# CW313_20_Pin_Connector.net
KiCad netlist of a schematic drawn in Altium Designer
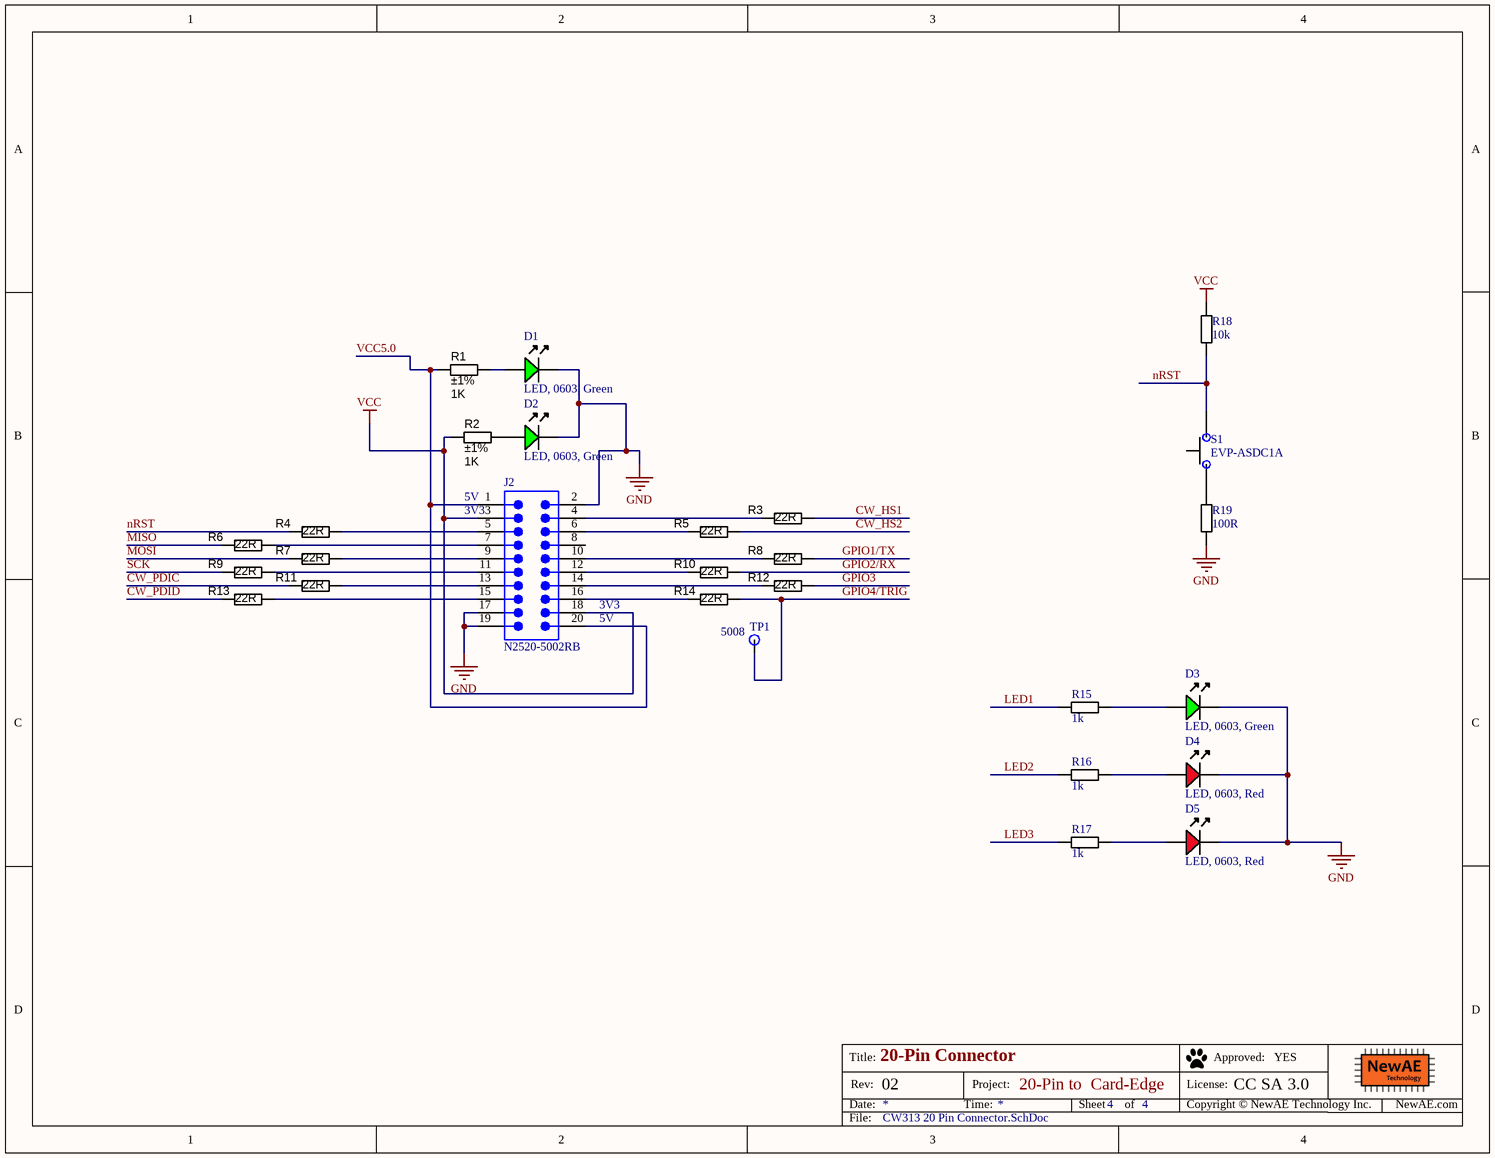
[diagram p0: CW313 20 Pin Connector.SchDoc]

(export (version "E")
  (design (tool "Eeschema 10.0.6"))
  (components
    (comp (ref "D1")
      (value "LED, 0603, Green")
      (footprint "LED-0603-GREEN")
      (description "Chip LED, Green")
      (fields (field (name "PART NUMBER") "LEDCHIP_0603_GREEN"))
      (libsource (lib "NewAE_AltiumLib") (part "LED_GREEN"))
    )
    (comp (ref "D2")
      (value "LED, 0603, Green")
      (footprint "LED-0603-GREEN")
      (description "Chip LED, Green")
      (fields (field (name "PART NUMBER") "LEDCHIP_0603_GREEN"))
      (libsource (lib "NewAE_AltiumLib") (part "LED_GREEN"))
    )
    (comp (ref "D3")
      (value "LED, 0603, Green")
      (footprint "LED-0603-GREEN")
      (description "Chip LED, Green")
      (fields (field (name "PART NUMBER") "LEDCHIP_0603_GREEN"))
      (libsource (lib "NewAE_AltiumLib") (part "LED_GREEN"))
    )
    (comp (ref "D4")
      (value "LED, 0603, Red")
      (footprint "LED-0603-RED")
      (description "Chip LED, Red")
      (fields (field (name "PART NUMBER") "LEDCHIP_0603_RED"))
      (libsource (lib "NewAE_AltiumLib") (part "LED_RED"))
    )
    (comp (ref "D5")
      (value "LED, 0603, Red")
      (footprint "LED-0603-RED")
      (description "Chip LED, Red")
      (fields (field (name "PART NUMBER") "LEDCHIP_0603_RED"))
      (libsource (lib "NewAE_AltiumLib") (part "LED_RED"))
    )
    (comp (ref "J2")
      (value "N2520-5002RB")
      (footprint "NAE-PCB-CW-1000-0001-01")
      (description "20 Pin R/A Shrouded Header")
      (fields (field (name "MANUFACTURER") "3M"))
      (libsource (lib "NewAE_AltiumLib") (part "NAE-CW-1000-0001-01"))
    )
    (comp (ref "R1")
      (value "1K")
      (footprint "RESC1608X55N")
      (description "Resistor SMD chip 1k Ohm 0.1W 1% 0603")
      (fields (field (name "TOLERANCE") "±1%") (field (name "Comment") "Thick Film"))
      (libsource (lib "PBL - Resistors") (part "RES_1K_0603_1%"))
    )
    (comp (ref "R2")
      (value "1K")
      (footprint "RESC1608X55N")
      (description "Resistor SMD chip 1k Ohm 0.1W 1% 0603")
      (fields (field (name "TOLERANCE") "±1%") (field (name "Comment") "Thick Film"))
      (libsource (lib "PBL - Resistors") (part "RES_1K_0603_1%"))
    )
    (comp (ref "R3")
      (value "22R")
      (footprint "RESC1608X55N")
      (description "Resistor SMD chip 22 Ohm 0.1W 5% 0603")
      (fields (field (name "TOLERANCE") "±5%") (field (name "Comment") "Thick Film"))
      (libsource (lib "PBL - Resistors") (part "RES_22R_0603_5%"))
    )
    (comp (ref "R4")
      (value "22R")
      (footprint "RESC1608X55N")
      (description "Resistor SMD chip 22 Ohm 0.1W 5% 0603")
      (fields (field (name "TOLERANCE") "±5%") (field (name "Comment") "Thick Film"))
      (libsource (lib "PBL - Resistors") (part "RES_22R_0603_5%"))
    )
    (comp (ref "R5")
      (value "22R")
      (footprint "RESC1608X55N")
      (description "Resistor SMD chip 22 Ohm 0.1W 5% 0603")
      (fields (field (name "TOLERANCE") "±5%") (field (name "Comment") "Thick Film"))
      (libsource (lib "PBL - Resistors") (part "RES_22R_0603_5%"))
    )
    (comp (ref "R6")
      (value "22R")
      (footprint "RESC1608X55N")
      (description "Resistor SMD chip 22 Ohm 0.1W 5% 0603")
      (fields (field (name "TOLERANCE") "±5%") (field (name "Comment") "Thick Film"))
      (libsource (lib "PBL - Resistors") (part "RES_22R_0603_5%"))
    )
    (comp (ref "R7")
      (value "22R")
      (footprint "RESC1608X55N")
      (description "Resistor SMD chip 22 Ohm 0.1W 5% 0603")
      (fields (field (name "TOLERANCE") "±5%") (field (name "Comment") "Thick Film"))
      (libsource (lib "PBL - Resistors") (part "RES_22R_0603_5%"))
    )
    (comp (ref "R8")
      (value "22R")
      (footprint "RESC1608X55N")
      (description "Resistor SMD chip 22 Ohm 0.1W 5% 0603")
      (fields (field (name "TOLERANCE") "±5%") (field (name "Comment") "Thick Film"))
      (libsource (lib "PBL - Resistors") (part "RES_22R_0603_5%"))
    )
    (comp (ref "R9")
      (value "22R")
      (footprint "RESC1608X55N")
      (description "Resistor SMD chip 22 Ohm 0.1W 5% 0603")
      (fields (field (name "TOLERANCE") "±5%") (field (name "Comment") "Thick Film"))
      (libsource (lib "PBL - Resistors") (part "RES_22R_0603_5%"))
    )
    (comp (ref "R10")
      (value "22R")
      (footprint "RESC1608X55N")
      (description "Resistor SMD chip 22 Ohm 0.1W 5% 0603")
      (fields (field (name "TOLERANCE") "±5%") (field (name "Comment") "Thick Film"))
      (libsource (lib "PBL - Resistors") (part "RES_22R_0603_5%"))
    )
    (comp (ref "R11")
      (value "22R")
      (footprint "RESC1608X55N")
      (description "Resistor SMD chip 22 Ohm 0.1W 5% 0603")
      (fields (field (name "TOLERANCE") "±5%") (field (name "Comment") "Thick Film"))
      (libsource (lib "PBL - Resistors") (part "RES_22R_0603_5%"))
    )
    (comp (ref "R12")
      (value "22R")
      (footprint "RESC1608X55N")
      (description "Resistor SMD chip 22 Ohm 0.1W 5% 0603")
      (fields (field (name "TOLERANCE") "±5%") (field (name "Comment") "Thick Film"))
      (libsource (lib "PBL - Resistors") (part "RES_22R_0603_5%"))
    )
    (comp (ref "R13")
      (value "22R")
      (footprint "RESC1608X55N")
      (description "Resistor SMD chip 22 Ohm 0.1W 5% 0603")
      (fields (field (name "TOLERANCE") "±5%") (field (name "Comment") "Thick Film"))
      (libsource (lib "PBL - Resistors") (part "RES_22R_0603_5%"))
    )
    (comp (ref "R14")
      (value "22R")
      (footprint "RESC1608X55N")
      (description "Resistor SMD chip 22 Ohm 0.1W 5% 0603")
      (fields (field (name "TOLERANCE") "±5%") (field (name "Comment") "Thick Film"))
      (libsource (lib "PBL - Resistors") (part "RES_22R_0603_5%"))
    )
    (comp (ref "R15")
      (value "1k")
      (footprint "RESC1608X55N")
      (description "1k res, 0603, 1%, 1/10W")
      (fields (field (name "PART NUMBER") "RCHIP-1K-0603") (field (name "TOLERANCE") "1%"))
      (libsource (lib "NewAE_AltiumLib") (part "RES-EU"))
    )
    (comp (ref "R16")
      (value "1k")
      (footprint "RESC1608X55N")
      (description "1k res, 0603, 1%, 1/10W")
      (fields (field (name "PART NUMBER") "RCHIP-1K-0603") (field (name "TOLERANCE") "1%"))
      (libsource (lib "NewAE_AltiumLib") (part "RES-EU"))
    )
    (comp (ref "R17")
      (value "1k")
      (footprint "RESC1608X55N")
      (description "1k res, 0603, 1%, 1/10W")
      (fields (field (name "PART NUMBER") "RCHIP-1K-0603") (field (name "TOLERANCE") "1%"))
      (libsource (lib "NewAE_AltiumLib") (part "RES-EU"))
    )
    (comp (ref "R18")
      (value "10k")
      (footprint "RESC1608X55N")
      (description "10k res, 0603, 1%, 1/10W")
      (fields (field (name "PART NUMBER") "RCHIP-10K-0603") (field (name "TOLERANCE") "1%"))
      (libsource (lib "") (part "RES-EU_1"))
    )
    (comp (ref "R19")
      (value "100R")
      (footprint "RESC1608X55N")
      (description "100R res, 0603, 1%, 1/10W")
      (fields (field (name "PART NUMBER") "RCHIP-100R-0603") (field (name "TOLERANCE") "1%"))
      (libsource (lib "") (part "RES-EU_1"))
    )
    (comp (ref "S1")
      (value "EVP-ASDC1A")
      (footprint "EVPAS")
      (description "Pushbutton, SMD, 2.5NM force, NO")
      (libsource (lib "NewAE_AltiumLib") (part "SW_PB_NO_2PIN"))
    )
    (comp (ref "TP1")
      (value "5008")
      (footprint "KEYSTONE5008")
      (description "TEST POINT PC COMPACT .063\"D ORG")
      (fields (field (name "PART NUMBER") "KEYSTONE_5008"))
      (libsource (lib "NewAE_AltiumLib") (part "KEYSTONE_5008"))
    )
  )
  (nets
    (net (code "1") (name "/CW_HS1") (class "Default")
      (node (ref "R3") (pin "2") (pinfunction "2_2") (pintype "passive"))
    )
    (net (code "2") (name "/CW_HS2") (class "Default")
      (node (ref "R5") (pin "2") (pinfunction "2_2") (pintype "passive"))
    )
    (net (code "3") (name "/CW_PDIC") (class "Default")
      (node (ref "R11") (pin "1") (pinfunction "1_1") (pintype "passive"))
    )
    (net (code "4") (name "/CW_PDID") (class "Default")
      (node (ref "R13") (pin "1") (pinfunction "1_1") (pintype "passive"))
    )
    (net (code "5") (name "/GPIO1{slash}TX") (class "Default")
      (node (ref "R8") (pin "2") (pinfunction "2_2") (pintype "passive"))
    )
    (net (code "6") (name "/GPIO2{slash}RX") (class "Default")
      (node (ref "R10") (pin "2") (pinfunction "2_2") (pintype "passive"))
    )
    (net (code "7") (name "/GPIO3") (class "Default")
      (node (ref "R12") (pin "2") (pinfunction "2_2") (pintype "passive"))
    )
    (net (code "8") (name "/GPIO4{slash}TRIG") (class "Default")
      (node (ref "R14") (pin "2") (pinfunction "2_2") (pintype "passive"))
      (node (ref "TP1") (pin "1") (pinfunction "1_1") (pintype "passive"))
    )
    (net (code "9") (name "/LED1") (class "Default")
      (node (ref "R15") (pin "1") (pinfunction "1_1") (pintype "passive"))
    )
    (net (code "10") (name "/LED2") (class "Default")
      (node (ref "R16") (pin "1") (pinfunction "1_1") (pintype "passive"))
    )
    (net (code "11") (name "/LED3") (class "Default")
      (node (ref "R17") (pin "1") (pinfunction "1_1") (pintype "passive"))
    )
    (net (code "12") (name "/MISO") (class "Default")
      (node (ref "R6") (pin "1") (pinfunction "1_1") (pintype "passive"))
    )
    (net (code "13") (name "/MOSI") (class "Default")
      (node (ref "R7") (pin "1") (pinfunction "1_1") (pintype "passive"))
    )
    (net (code "14") (name "/SCK") (class "Default")
      (node (ref "R9") (pin "1") (pinfunction "1_1") (pintype "passive"))
    )
    (net (code "15") (name "/VCC5.0") (class "Default")
      (node (ref "J2") (pin "1") (pinfunction "1_1") (pintype "passive"))
      (node (ref "J2") (pin "20") (pinfunction "20_20") (pintype "passive"))
      (node (ref "R1") (pin "2") (pinfunction "2_2") (pintype "passive"))
    )
    (net (code "16") (name "/nRST") (class "Default")
      (node (ref "R18") (pin "2") (pinfunction "2_2") (pintype "passive"))
      (node (ref "R4") (pin "1") (pinfunction "1_1") (pintype "passive"))
      (node (ref "S1") (pin "2") (pinfunction "IN_2") (pintype "passive"))
    )
    (net (code "17") (name "GND") (class "Default")
      (node (ref "D1") (pin "K") (pinfunction "K_K") (pintype "passive"))
      (node (ref "D2") (pin "K") (pinfunction "K_K") (pintype "passive"))
      (node (ref "D3") (pin "K") (pinfunction "K_K") (pintype "passive"))
      (node (ref "D4") (pin "K") (pinfunction "K_K") (pintype "passive"))
      (node (ref "D5") (pin "K") (pinfunction "K_K") (pintype "passive"))
      (node (ref "J2") (pin "17") (pinfunction "17_17") (pintype "passive"))
      (node (ref "J2") (pin "19") (pinfunction "19_19") (pintype "passive"))
      (node (ref "J2") (pin "2") (pinfunction "2_2") (pintype "passive"))
      (node (ref "R19") (pin "2") (pinfunction "2_2") (pintype "passive"))
    )
    (net (code "18") (name "Net-(D1-PadA)") (class "Default")
      (node (ref "D1") (pin "A") (pinfunction "A_A") (pintype "passive"))
      (node (ref "R1") (pin "1") (pinfunction "1_1") (pintype "passive"))
    )
    (net (code "19") (name "Net-(D2-PadA)") (class "Default")
      (node (ref "D2") (pin "A") (pinfunction "A_A") (pintype "passive"))
      (node (ref "R2") (pin "1") (pinfunction "1_1") (pintype "passive"))
    )
    (net (code "20") (name "Net-(D3-PadA)") (class "Default")
      (node (ref "D3") (pin "A") (pinfunction "A_A") (pintype "passive"))
      (node (ref "R15") (pin "2") (pinfunction "2_2") (pintype "passive"))
    )
    (net (code "21") (name "Net-(D4-PadA)") (class "Default")
      (node (ref "D4") (pin "A") (pinfunction "A_A") (pintype "passive"))
      (node (ref "R16") (pin "2") (pinfunction "2_2") (pintype "passive"))
    )
    (net (code "22") (name "Net-(D5-PadA)") (class "Default")
      (node (ref "D5") (pin "A") (pinfunction "A_A") (pintype "passive"))
      (node (ref "R17") (pin "2") (pinfunction "2_2") (pintype "passive"))
    )
    (net (code "23") (name "Net-(J2-Pad4)") (class "Default")
      (node (ref "J2") (pin "4") (pinfunction "4_4") (pintype "passive"))
      (node (ref "R3") (pin "1") (pinfunction "1_1") (pintype "passive"))
    )
    (net (code "24") (name "Net-(J2-Pad5)") (class "Default")
      (node (ref "J2") (pin "5") (pinfunction "5_5") (pintype "passive"))
      (node (ref "R4") (pin "2") (pinfunction "2_2") (pintype "passive"))
    )
    (net (code "25") (name "Net-(J2-Pad6)") (class "Default")
      (node (ref "J2") (pin "6") (pinfunction "6_6") (pintype "passive"))
      (node (ref "R5") (pin "1") (pinfunction "1_1") (pintype "passive"))
    )
    (net (code "26") (name "Net-(J2-Pad7)") (class "Default")
      (node (ref "J2") (pin "7") (pinfunction "7_7") (pintype "passive"))
      (node (ref "R6") (pin "2") (pinfunction "2_2") (pintype "passive"))
    )
    (net (code "27") (name "Net-(J2-Pad9)") (class "Default")
      (node (ref "J2") (pin "9") (pinfunction "9_9") (pintype "passive"))
      (node (ref "R7") (pin "2") (pinfunction "2_2") (pintype "passive"))
    )
    (net (code "28") (name "Net-(J2-Pad10)") (class "Default")
      (node (ref "J2") (pin "10") (pinfunction "10_10") (pintype "passive"))
      (node (ref "R8") (pin "1") (pinfunction "1_1") (pintype "passive"))
    )
    (net (code "29") (name "Net-(J2-Pad11)") (class "Default")
      (node (ref "J2") (pin "11") (pinfunction "11_11") (pintype "passive"))
      (node (ref "R9") (pin "2") (pinfunction "2_2") (pintype "passive"))
    )
    (net (code "30") (name "Net-(J2-Pad12)") (class "Default")
      (node (ref "J2") (pin "12") (pinfunction "12_12") (pintype "passive"))
      (node (ref "R10") (pin "1") (pinfunction "1_1") (pintype "passive"))
    )
    (net (code "31") (name "Net-(J2-Pad13)") (class "Default")
      (node (ref "J2") (pin "13") (pinfunction "13_13") (pintype "passive"))
      (node (ref "R11") (pin "2") (pinfunction "2_2") (pintype "passive"))
    )
    (net (code "32") (name "Net-(J2-Pad14)") (class "Default")
      (node (ref "J2") (pin "14") (pinfunction "14_14") (pintype "passive"))
      (node (ref "R12") (pin "1") (pinfunction "1_1") (pintype "passive"))
    )
    (net (code "33") (name "Net-(J2-Pad15)") (class "Default")
      (node (ref "J2") (pin "15") (pinfunction "15_15") (pintype "passive"))
      (node (ref "R13") (pin "2") (pinfunction "2_2") (pintype "passive"))
    )
    (net (code "34") (name "Net-(J2-Pad16)") (class "Default")
      (node (ref "J2") (pin "16") (pinfunction "16_16") (pintype "passive"))
      (node (ref "R14") (pin "1") (pinfunction "1_1") (pintype "passive"))
    )
    (net (code "35") (name "Net-(R19-Pad1)") (class "Default")
      (node (ref "R19") (pin "1") (pinfunction "1_1") (pintype "passive"))
      (node (ref "S1") (pin "1") (pinfunction "IN_1") (pintype "passive"))
    )
    (net (code "36") (name "VCC") (class "Default")
      (node (ref "J2") (pin "18") (pinfunction "18_18") (pintype "passive"))
      (node (ref "J2") (pin "3") (pinfunction "3_3") (pintype "passive"))
      (node (ref "R18") (pin "1") (pinfunction "1_1") (pintype "passive"))
      (node (ref "R2") (pin "2") (pinfunction "2_2") (pintype "passive"))
    )
    (net (code "37") (name "unconnected-(J2-Pad8)") (class "Default")
      (node (ref "J2") (pin "8") (pinfunction "8_8") (pintype "passive"))
    )
  )
)
